# Main.net
KiCad netlist of a schematic drawn in Altium Designer
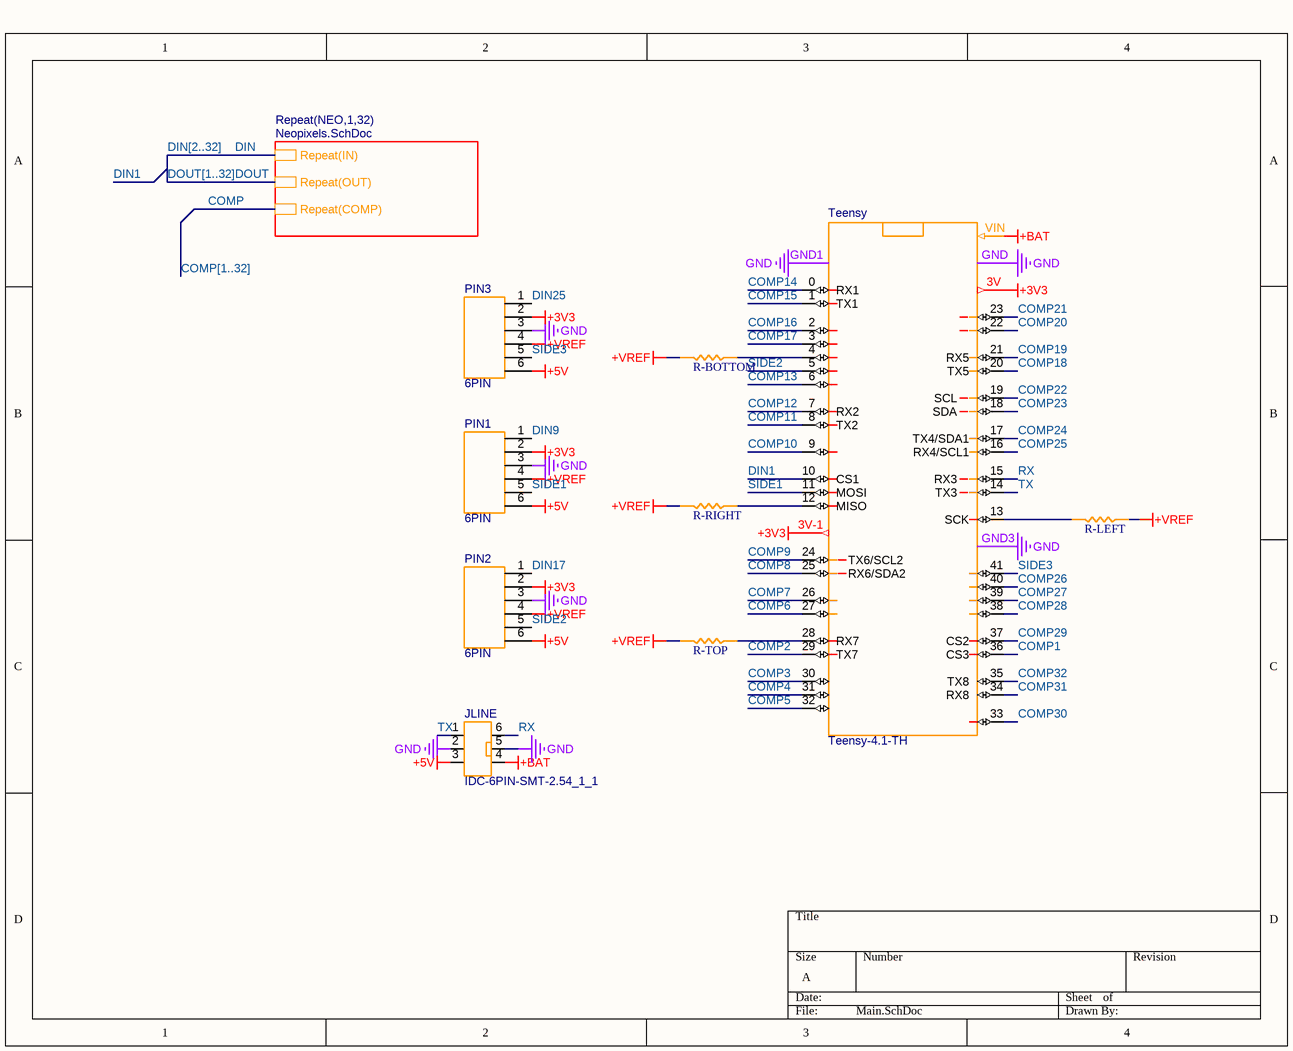
[diagram p0: Main.SchDoc]

(export (version "E")
  (design (tool "Eeschema 10.0.6"))
  (components
    (comp (ref "JLINE")
      (value "IDC-6PIN-SMT-2.54_1_1")
      (footprint "IDC-6PIN-SMT-2.54")
      (libsource (lib "RC") (part "IDC-6PIN-SMT-2.54_1_1"))
    )
    (comp (ref "PIN1") (value "6PIN") (footprint "6PIN") (libsource (lib "RC") (part "6PIN")))
    (comp (ref "PIN2") (value "6PIN") (footprint "6PIN") (libsource (lib "RC") (part "6PIN")))
    (comp (ref "PIN3") (value "6PIN") (footprint "6PIN") (libsource (lib "RC") (part "6PIN")))
    (comp (ref "R-BOTTOM")
      (value "RES_0603")
      (footprint "RES_0603")
      (description "Resistor SMD 0603 generic")
      (libsource (lib "ChaBots Phoenix") (part "RES_0603"))
    )
    (comp (ref "R-LEFT")
      (value "RES_0603")
      (footprint "RES_0603")
      (description "Resistor SMD 0603 generic")
      (libsource (lib "ChaBots Phoenix") (part "RES_0603"))
    )
    (comp (ref "R-RIGHT")
      (value "RES_0603")
      (footprint "RES_0603")
      (description "Resistor SMD 0603 generic")
      (libsource (lib "ChaBots Phoenix") (part "RES_0603"))
    )
    (comp (ref "R-TOP")
      (value "RES_0603")
      (footprint "RES_0603")
      (description "Resistor SMD 0603 generic")
      (libsource (lib "ChaBots Phoenix") (part "RES_0603"))
    )
    (comp (ref "Teensy")
      (value "Teensy-4.1-TH")
      (footprint "Teensy-4.1-TH")
      (libsource (lib "RC") (part "Teensy-4.1-TH"))
    )
  )
  (nets
    (net (code "29") (name "+3V3") (class "Default")
      (node (ref "PIN1") (pin "2") (pinfunction "02_2") (pintype "passive"))
      (node (ref "PIN2") (pin "2") (pinfunction "02_2") (pintype "passive"))
      (node (ref "PIN3") (pin "2") (pinfunction "02_2") (pintype "passive"))
      (node (ref "Teensy") (pin "3V") (pintype "output"))
      (node (ref "Teensy") (pin "3V-1") (pintype "output"))
    )
    (net (code "30") (name "+5V") (class "Default")
      (node (ref "JLINE") (pin "3") (pintype "passive"))
      (node (ref "PIN1") (pin "6") (pinfunction "06_6") (pintype "passive"))
      (node (ref "PIN2") (pin "6") (pinfunction "06_6") (pintype "passive"))
      (node (ref "PIN3") (pin "6") (pinfunction "06_6") (pintype "passive"))
    )
    (net (code "31") (name "+BAT") (class "Default")
      (node (ref "JLINE") (pin "4") (pintype "passive"))
      (node (ref "Teensy") (pin "VIN") (pintype "input"))
    )
    (net (code "32") (name "+VREF") (class "Default")
      (node (ref "PIN1") (pin "4") (pinfunction "04_4") (pintype "passive"))
      (node (ref "PIN2") (pin "4") (pinfunction "04_4") (pintype "passive"))
      (node (ref "PIN3") (pin "4") (pinfunction "04_4") (pintype "passive"))
      (node (ref "R-BOTTOM") (pin "1") (pintype "passive"))
      (node (ref "R-LEFT") (pin "2") (pintype "passive"))
      (node (ref "R-RIGHT") (pin "1") (pintype "passive"))
      (node (ref "R-TOP") (pin "1") (pintype "passive"))
    )
    (net (code "35") (name "/COMP1") (class "Default")
      (node (ref "Teensy") (pin "36") (pinfunction "CS3_36") (pintype "bidirectional"))
    )
    (net (code "36") (name "/COMP2") (class "Default")
      (node (ref "Teensy") (pin "29") (pinfunction "TX7_29") (pintype "bidirectional"))
    )
    (net (code "37") (name "/COMP3") (class "Default")
      (node (ref "Teensy") (pin "30") (pintype "bidirectional"))
    )
    (net (code "38") (name "/COMP4") (class "Default")
      (node (ref "Teensy") (pin "31") (pintype "bidirectional"))
    )
    (net (code "39") (name "/COMP5") (class "Default")
      (node (ref "Teensy") (pin "32") (pintype "bidirectional"))
    )
    (net (code "40") (name "/COMP6") (class "Default")
      (node (ref "Teensy") (pin "27") (pintype "bidirectional"))
    )
    (net (code "41") (name "/COMP7") (class "Default")
      (node (ref "Teensy") (pin "26") (pintype "bidirectional"))
    )
    (net (code "42") (name "/COMP8") (class "Default")
      (node (ref "Teensy") (pin "25") (pinfunction "RX6/SDA2_25") (pintype "bidirectional"))
    )
    (net (code "43") (name "/COMP9") (class "Default")
      (node (ref "Teensy") (pin "24") (pinfunction "TX6/SCL2_24") (pintype "bidirectional"))
    )
    (net (code "44") (name "/COMP10") (class "Default")
      (node (ref "Teensy") (pin "9") (pintype "bidirectional"))
    )
    (net (code "45") (name "/COMP11") (class "Default")
      (node (ref "Teensy") (pin "8") (pinfunction "TX2_8") (pintype "bidirectional"))
    )
    (net (code "46") (name "/COMP12") (class "Default")
      (node (ref "Teensy") (pin "7") (pinfunction "RX2_7") (pintype "bidirectional"))
    )
    (net (code "47") (name "/COMP13") (class "Default")
      (node (ref "Teensy") (pin "6") (pintype "bidirectional"))
    )
    (net (code "48") (name "/COMP14") (class "Default")
      (node (ref "Teensy") (pin "0") (pinfunction "RX1_0") (pintype "bidirectional"))
    )
    (net (code "49") (name "/COMP15") (class "Default")
      (node (ref "Teensy") (pin "1") (pinfunction "TX1_1") (pintype "bidirectional"))
    )
    (net (code "50") (name "/COMP16") (class "Default")
      (node (ref "Teensy") (pin "2") (pintype "bidirectional"))
    )
    (net (code "51") (name "/COMP17") (class "Default")
      (node (ref "Teensy") (pin "3") (pintype "bidirectional"))
    )
    (net (code "52") (name "/COMP18") (class "Default")
      (node (ref "Teensy") (pin "20") (pinfunction "TX5_20") (pintype "bidirectional"))
    )
    (net (code "53") (name "/COMP19") (class "Default")
      (node (ref "Teensy") (pin "21") (pinfunction "RX5_21") (pintype "bidirectional"))
    )
    (net (code "54") (name "/COMP20") (class "Default")
      (node (ref "Teensy") (pin "22") (pintype "bidirectional"))
    )
    (net (code "55") (name "/COMP21") (class "Default")
      (node (ref "Teensy") (pin "23") (pintype "bidirectional"))
    )
    (net (code "56") (name "/COMP22") (class "Default")
      (node (ref "Teensy") (pin "19") (pinfunction "SCL_19") (pintype "bidirectional"))
    )
    (net (code "57") (name "/COMP23") (class "Default")
      (node (ref "Teensy") (pin "18") (pinfunction "SDA_18") (pintype "bidirectional"))
    )
    (net (code "58") (name "/COMP24") (class "Default")
      (node (ref "Teensy") (pin "17") (pinfunction "TX4/SDA1_17") (pintype "bidirectional"))
    )
    (net (code "59") (name "/COMP25") (class "Default")
      (node (ref "Teensy") (pin "16") (pinfunction "RX4/SCL1_16") (pintype "bidirectional"))
    )
    (net (code "60") (name "/COMP26") (class "Default")
      (node (ref "Teensy") (pin "40") (pintype "bidirectional"))
    )
    (net (code "61") (name "/COMP27") (class "Default")
      (node (ref "Teensy") (pin "39") (pintype "bidirectional"))
    )
    (net (code "62") (name "/COMP28") (class "Default")
      (node (ref "Teensy") (pin "38") (pintype "bidirectional"))
    )
    (net (code "63") (name "/COMP29") (class "Default")
      (node (ref "Teensy") (pin "37") (pinfunction "CS2_37") (pintype "bidirectional"))
    )
    (net (code "64") (name "/COMP30") (class "Default")
      (node (ref "Teensy") (pin "33") (pintype "bidirectional"))
    )
    (net (code "65") (name "/COMP31") (class "Default")
      (node (ref "Teensy") (pin "34") (pinfunction "RX8_34") (pintype "bidirectional"))
    )
    (net (code "66") (name "/COMP32") (class "Default")
      (node (ref "Teensy") (pin "35") (pinfunction "TX8_35") (pintype "bidirectional"))
    )
    (net (code "69") (name "/DIN1") (class "Default")
      (node (ref "Teensy") (pin "10") (pinfunction "CS1_10") (pintype "bidirectional"))
    )
    (net (code "70") (name "/DIN9") (class "Default")
      (node (ref "PIN1") (pin "1") (pinfunction "01_1") (pintype "passive"))
    )
    (net (code "71") (name "/DIN17") (class "Default")
      (node (ref "PIN2") (pin "1") (pinfunction "01_1") (pintype "passive"))
    )
    (net (code "72") (name "/DIN25") (class "Default")
      (node (ref "PIN3") (pin "1") (pinfunction "01_1") (pintype "passive"))
    )
    (net (code "75") (name "/RX") (class "Default")
      (node (ref "JLINE") (pin "6") (pintype "passive"))
      (node (ref "Teensy") (pin "15") (pinfunction "RX3_15") (pintype "bidirectional"))
    )
    (net (code "76") (name "/SIDE1") (class "Default")
      (node (ref "PIN1") (pin "5") (pinfunction "05_5") (pintype "passive"))
      (node (ref "Teensy") (pin "11") (pinfunction "MOSI_11") (pintype "bidirectional"))
    )
    (net (code "77") (name "/SIDE2") (class "Default")
      (node (ref "PIN2") (pin "5") (pinfunction "05_5") (pintype "passive"))
      (node (ref "Teensy") (pin "5") (pintype "bidirectional"))
    )
    (net (code "78") (name "/SIDE3") (class "Default")
      (node (ref "PIN3") (pin "5") (pinfunction "05_5") (pintype "passive"))
      (node (ref "Teensy") (pin "41") (pintype "bidirectional"))
    )
    (net (code "79") (name "/TX") (class "Default")
      (node (ref "JLINE") (pin "1") (pintype "passive"))
      (node (ref "Teensy") (pin "14") (pinfunction "TX3_14") (pintype "bidirectional"))
    )
    (net (code "80") (name "GND") (class "Default")
      (node (ref "JLINE") (pin "2") (pintype "passive"))
      (node (ref "JLINE") (pin "5") (pintype "passive"))
      (node (ref "PIN1") (pin "3") (pinfunction "03_3") (pintype "passive"))
      (node (ref "PIN2") (pin "3") (pinfunction "03_3") (pintype "passive"))
      (node (ref "PIN3") (pin "3") (pinfunction "03_3") (pintype "passive"))
      (node (ref "Teensy") (pin "GND") (pintype "passive"))
      (node (ref "Teensy") (pin "GND1") (pintype "passive"))
      (node (ref "Teensy") (pin "GND3") (pintype "power_in"))
    )
    (net (code "81") (name "Net-(R-BOTTOM-Pad2)") (class "Default")
      (node (ref "R-BOTTOM") (pin "2") (pintype "passive"))
      (node (ref "Teensy") (pin "4") (pintype "bidirectional"))
    )
    (net (code "82") (name "Net-(Teensy-MISO)") (class "Default")
      (node (ref "R-RIGHT") (pin "2") (pintype "passive"))
      (node (ref "Teensy") (pin "12") (pinfunction "MISO_12") (pintype "bidirectional"))
    )
    (net (code "83") (name "Net-(Teensy-RX7)") (class "Default")
      (node (ref "R-TOP") (pin "2") (pintype "passive"))
      (node (ref "Teensy") (pin "28") (pinfunction "RX7_28") (pintype "bidirectional"))
    )
    (net (code "84") (name "Net-(Teensy-SCK)") (class "Default")
      (node (ref "R-LEFT") (pin "1") (pintype "passive"))
      (node (ref "Teensy") (pin "13") (pinfunction "SCK_13") (pintype "bidirectional"))
    )
  )
)
